# MCU.net
KiCad netlist of a schematic drawn in Altium Designer
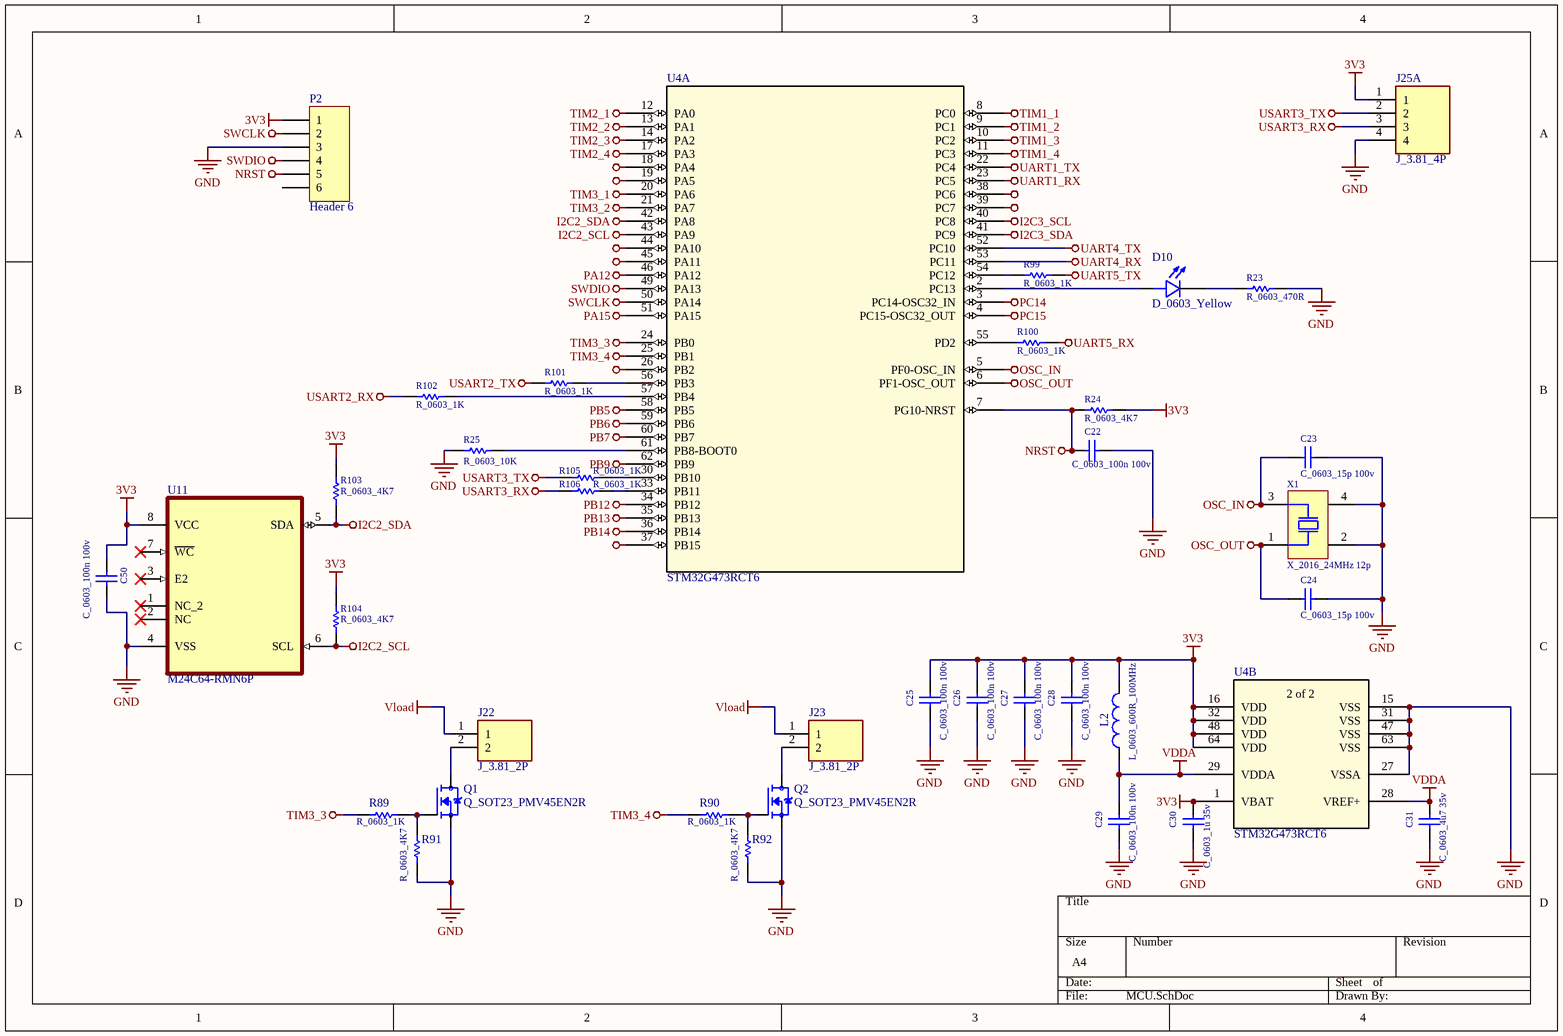
[diagram p0: MCU.SchDoc]

(export (version "E")
  (design (tool "Eeschema 10.0.6"))
  (components
    (comp (ref "C22")
      (value "C_0603_100n 100v")
      (footprint "CAP 0603")
      (description "Capacitor")
      (fields (field (name "PUBLISHER") "Altium Limited"))
      (libsource (lib "HUE") (part "Cap"))
    )
    (comp (ref "C23")
      (value "C_0603_15p 100v")
      (footprint "CAP 0603")
      (description "Capacitor")
      (fields (field (name "PUBLISHER") "Altium Limited"))
      (libsource (lib "HUE") (part "Cap"))
    )
    (comp (ref "C24")
      (value "C_0603_15p 100v")
      (footprint "CAP 0603")
      (description "Capacitor")
      (fields (field (name "PUBLISHER") "Altium Limited"))
      (libsource (lib "HUE") (part "Cap"))
    )
    (comp (ref "C25")
      (value "C_0603_100n 100v")
      (footprint "CAP 0603")
      (description "Capacitor")
      (fields (field (name "PUBLISHER") "Altium Limited"))
      (libsource (lib "HUE") (part "Cap"))
    )
    (comp (ref "C26")
      (value "C_0603_100n 100v")
      (footprint "CAP 0603")
      (description "Capacitor")
      (fields (field (name "PUBLISHER") "Altium Limited"))
      (libsource (lib "HUE") (part "Cap"))
    )
    (comp (ref "C27")
      (value "C_0603_100n 100v")
      (footprint "CAP 0603")
      (description "Capacitor")
      (fields (field (name "PUBLISHER") "Altium Limited"))
      (libsource (lib "HUE") (part "Cap"))
    )
    (comp (ref "C28")
      (value "C_0603_100n 100v")
      (footprint "CAP 0603")
      (description "Capacitor")
      (fields (field (name "PUBLISHER") "Altium Limited"))
      (libsource (lib "HUE") (part "Cap"))
    )
    (comp (ref "C29")
      (value "C_0603_100n 100v")
      (footprint "CAP 0603")
      (description "Capacitor")
      (fields (field (name "PUBLISHER") "Altium Limited"))
      (libsource (lib "HUE") (part "Cap"))
    )
    (comp (ref "C30")
      (value "C_0603_1u 35v")
      (footprint "CAP 0603")
      (description "Capacitor")
      (fields (field (name "PUBLISHER") "Altium Limited"))
      (libsource (lib "HUE") (part "Cap"))
    )
    (comp (ref "C31")
      (value "C_0603_4u7 35v")
      (footprint "CAP 0603")
      (description "Capacitor")
      (fields (field (name "PUBLISHER") "Altium Limited"))
      (libsource (lib "HUE") (part "Cap"))
    )
    (comp (ref "C50")
      (value "C_0603_100n 100v")
      (footprint "CAP 0603")
      (description "Capacitor")
      (fields (field (name "PUBLISHER") "Altium Limited"))
      (libsource (lib "HUE") (part "Cap"))
    )
    (comp (ref "D10")
      (value "D_0603_Yellow")
      (footprint "Led 0603")
      (description "Led")
      (fields (field (name "MP") "SML-D12FWT86") (field (name "MF") "Rohm"))
      (libsource (lib "HUE") (part "Led"))
    )
    (comp (ref "J22")
      (value "J_3.81_2P")
      (footprint "2 Pin PCB TB 3.81")
      (fields (field (name "MF") "CUI Devices") (field (name "MP") "TBP02R1-381-02BE"))
      (libsource (lib "HUE") (part "2 Pin PCB Terminal Block"))
    )
    (comp (ref "J23")
      (value "J_3.81_2P")
      (footprint "2 Pin PCB TB 3.81")
      (fields (field (name "MF") "CUI Devices") (field (name "MP") "TBP02R1-381-02BE"))
      (libsource (lib "HUE") (part "2 Pin PCB Terminal Block"))
    )
    (comp (ref "J25")
      (value "J_3.81_4P")
      (footprint "4 Pin PCB TB 3.81")
      (fields (field (name "MP") "TBP02R1-381-04BE"))
      (libsource (lib "HUE") (part "4 Pin PCB Terminal Block"))
    )
    (comp (ref "L2")
      (value "L_0603_600R_100MHz")
      (footprint "Inductor 0603")
      (description "Inductor")
      (fields (field (name "PUBLISHER") "Altium Limited"))
      (libsource (lib "HUE") (part "Inductor"))
    )
    (comp (ref "P2")
      (value "Header 6")
      (footprint "HDR1X6")
      (description "Header, 6-Pin")
      (fields (field (name "PUBLISHER") "Altium Limited"))
      (libsource (lib "Miscellaneous Connectors") (part "Header 6"))
    )
    (comp (ref "Q1")
      (value "Q_SOT23_PMV45EN2R")
      (footprint "SOT23")
      (fields (field (name "MP") "IRLR2705PBF") (field (name "MF") "Infineon Technologies"))
      (libsource (lib "HUE") (part "N Channel Mosfet"))
    )
    (comp (ref "Q2")
      (value "Q_SOT23_PMV45EN2R")
      (footprint "SOT23")
      (fields (field (name "MP") "IRLR2705PBF") (field (name "MF") "Infineon Technologies"))
      (libsource (lib "HUE") (part "N Channel Mosfet"))
    )
    (comp (ref "R23")
      (value "R_0603_470R")
      (footprint "RES 0603")
      (description "Resistor")
      (fields (field (name "PUBLISHER") "Altium Limited"))
      (libsource (lib "HUE") (part "Res"))
    )
    (comp (ref "R24")
      (value "R_0603_4K7")
      (footprint "RES 0603")
      (description "Resistor")
      (fields (field (name "PUBLISHER") "Altium Limited"))
      (libsource (lib "HUE") (part "Res"))
    )
    (comp (ref "R25")
      (value "R_0603_10K")
      (footprint "RES 0603")
      (description "Resistor")
      (fields (field (name "PUBLISHER") "Altium Limited"))
      (libsource (lib "HUE") (part "Res"))
    )
    (comp (ref "R89")
      (value "R_0603_1K")
      (footprint "RES 0603")
      (description "Resistor")
      (fields (field (name "PUBLISHER") "Altium Limited"))
      (libsource (lib "HUE") (part "Res"))
    )
    (comp (ref "R90")
      (value "R_0603_1K")
      (footprint "RES 0603")
      (description "Resistor")
      (fields (field (name "PUBLISHER") "Altium Limited"))
      (libsource (lib "HUE") (part "Res"))
    )
    (comp (ref "R91")
      (value "R_0603_4K7")
      (footprint "RES 0603")
      (description "Resistor")
      (fields (field (name "PUBLISHER") "Altium Limited"))
      (libsource (lib "HUE") (part "Res"))
    )
    (comp (ref "R92")
      (value "R_0603_4K7")
      (footprint "RES 0603")
      (description "Resistor")
      (fields (field (name "PUBLISHER") "Altium Limited"))
      (libsource (lib "HUE") (part "Res"))
    )
    (comp (ref "R99")
      (value "R_0603_1K")
      (footprint "RES 0603")
      (description "Resistor")
      (fields (field (name "PUBLISHER") "Altium Limited"))
      (libsource (lib "HUE") (part "Res"))
    )
    (comp (ref "R100")
      (value "R_0603_1K")
      (footprint "RES 0603")
      (description "Resistor")
      (fields (field (name "PUBLISHER") "Altium Limited"))
      (libsource (lib "HUE") (part "Res"))
    )
    (comp (ref "R101")
      (value "R_0603_1K")
      (footprint "RES 0603")
      (description "Resistor")
      (fields (field (name "PUBLISHER") "Altium Limited"))
      (libsource (lib "HUE") (part "Res"))
    )
    (comp (ref "R102")
      (value "R_0603_1K")
      (footprint "RES 0603")
      (description "Resistor")
      (fields (field (name "PUBLISHER") "Altium Limited"))
      (libsource (lib "HUE") (part "Res"))
    )
    (comp (ref "R103")
      (value "R_0603_4K7")
      (footprint "RES 0603")
      (description "Resistor")
      (fields (field (name "PUBLISHER") "Altium Limited"))
      (libsource (lib "HUE") (part "Res"))
    )
    (comp (ref "R104")
      (value "R_0603_4K7")
      (footprint "RES 0603")
      (description "Resistor")
      (fields (field (name "PUBLISHER") "Altium Limited"))
      (libsource (lib "HUE") (part "Res"))
    )
    (comp (ref "R105")
      (value "R_0603_1K")
      (footprint "RES 0603")
      (description "Resistor")
      (fields (field (name "PUBLISHER") "Altium Limited"))
      (libsource (lib "HUE") (part "Res"))
    )
    (comp (ref "R106")
      (value "R_0603_1K")
      (footprint "RES 0603")
      (description "Resistor")
      (fields (field (name "PUBLISHER") "Altium Limited"))
      (libsource (lib "HUE") (part "Res"))
    )
    (comp (ref "U4")
      (value "STM32G473RCT6")
      (footprint "LQFP64")
      (description "No Description Available")
      (libsource (lib "HUE") (part "STM32G473RCT6"))
    )
    (comp (ref "U11")
      (value "M24C64-RMN6P")
      (footprint "SOIC8 - NO-EXP")
      (description "EEPROM")
      (libsource (lib "HUE") (part "M24C64-RMN6P"))
    )
    (comp (ref "X1")
      (value "X_2016_24MHz 12p")
      (footprint "Crystal 2016")
      (description "Crystal 4 Pin")
      (libsource (lib "HUE") (part "Crystal 4 Pin"))
    )
  )
  (nets
    (net (code "1") (name "3V3") (class "Default")
      (node (ref "C25") (pin "2") (pinfunction "2_2") (pintype "passive"))
      (node (ref "C26") (pin "2") (pinfunction "2_2") (pintype "passive"))
      (node (ref "C27") (pin "2") (pinfunction "2_2") (pintype "passive"))
      (node (ref "C28") (pin "2") (pinfunction "2_2") (pintype "passive"))
      (node (ref "C30") (pin "1") (pinfunction "1_1") (pintype "passive"))
      (node (ref "C50") (pin "1") (pinfunction "1_1") (pintype "passive"))
      (node (ref "J25") (pin "1") (pinfunction "1_1") (pintype "passive"))
      (node (ref "L2") (pin "2") (pinfunction "2_2") (pintype "passive"))
      (node (ref "P2") (pin "1") (pinfunction "1_1") (pintype "passive"))
      (node (ref "R103") (pin "2") (pinfunction "2_2") (pintype "passive"))
      (node (ref "R104") (pin "2") (pinfunction "2_2") (pintype "passive"))
      (node (ref "R24") (pin "1") (pinfunction "1_1") (pintype "passive"))
      (node (ref "U11") (pin "8") (pinfunction "VCC_8") (pintype "power_in"))
      (node (ref "U4") (pin "1") (pinfunction "VBAT_1") (pintype "power_in"))
      (node (ref "U4") (pin "16") (pinfunction "VDD_16") (pintype "power_in"))
      (node (ref "U4") (pin "32") (pinfunction "VDD_32") (pintype "power_in"))
      (node (ref "U4") (pin "48") (pinfunction "VDD_48") (pintype "power_in"))
      (node (ref "U4") (pin "64") (pinfunction "VDD_64") (pintype "power_in"))
    )
    (net (code "2") (name "<NO NET>") (class "Default")
      (node (ref "U4") (pin "18") (pinfunction "PA4_18") (pintype "bidirectional"))
      (node (ref "U4") (pin "19") (pinfunction "PA5_19") (pintype "bidirectional"))
      (node (ref "U4") (pin "26") (pinfunction "PB2_26") (pintype "bidirectional"))
      (node (ref "U4") (pin "37") (pinfunction "PB15_37") (pintype "bidirectional"))
      (node (ref "U4") (pin "38") (pinfunction "PC6_38") (pintype "bidirectional"))
      (node (ref "U4") (pin "39") (pinfunction "PC7_39") (pintype "bidirectional"))
      (node (ref "U4") (pin "44") (pinfunction "PA10_44") (pintype "bidirectional"))
      (node (ref "U4") (pin "45") (pinfunction "PA11_45") (pintype "bidirectional"))
    )
    (net (code "3") (name "GND") (class "Default")
      (node (ref "C22") (pin "1") (pinfunction "1_1") (pintype "passive"))
      (node (ref "C23") (pin "1") (pinfunction "1_1") (pintype "passive"))
      (node (ref "C24") (pin "1") (pinfunction "1_1") (pintype "passive"))
      (node (ref "C25") (pin "1") (pinfunction "1_1") (pintype "passive"))
      (node (ref "C26") (pin "1") (pinfunction "1_1") (pintype "passive"))
      (node (ref "C27") (pin "1") (pinfunction "1_1") (pintype "passive"))
      (node (ref "C28") (pin "1") (pinfunction "1_1") (pintype "passive"))
      (node (ref "C29") (pin "2") (pinfunction "2_2") (pintype "passive"))
      (node (ref "C30") (pin "2") (pinfunction "2_2") (pintype "passive"))
      (node (ref "C31") (pin "2") (pinfunction "2_2") (pintype "passive"))
      (node (ref "C50") (pin "2") (pinfunction "2_2") (pintype "passive"))
      (node (ref "J25") (pin "4") (pinfunction "4_4") (pintype "passive"))
      (node (ref "P2") (pin "3") (pinfunction "3_3") (pintype "passive"))
      (node (ref "Q1") (pin "2") (pinfunction "S_2") (pintype "passive"))
      (node (ref "Q2") (pin "2") (pinfunction "S_2") (pintype "passive"))
      (node (ref "R23") (pin "1") (pinfunction "1_1") (pintype "passive"))
      (node (ref "R25") (pin "1") (pinfunction "1_1") (pintype "passive"))
      (node (ref "R91") (pin "1") (pinfunction "1_1") (pintype "passive"))
      (node (ref "R92") (pin "1") (pinfunction "1_1") (pintype "passive"))
      (node (ref "U11") (pin "4") (pinfunction "VSS_4") (pintype "passive"))
      (node (ref "U4") (pin "15") (pinfunction "VSS_15") (pintype "power_in"))
      (node (ref "U4") (pin "27") (pinfunction "VSSA_27") (pintype "power_in"))
      (node (ref "U4") (pin "31") (pinfunction "VSS_31") (pintype "power_in"))
      (node (ref "U4") (pin "47") (pinfunction "VSS_47") (pintype "power_in"))
      (node (ref "U4") (pin "63") (pinfunction "VSS_63") (pintype "power_in"))
      (node (ref "X1") (pin "2") (pinfunction "NC_2") (pintype "passive"))
      (node (ref "X1") (pin "4") (pinfunction "NC_4") (pintype "passive"))
    )
    (net (code "4") (name "I2C2_SCL") (class "Default")
      (node (ref "R104") (pin "1") (pinfunction "1_1") (pintype "passive"))
      (node (ref "U11") (pin "6") (pinfunction "SCL_6") (pintype "input"))
      (node (ref "U4") (pin "43") (pinfunction "PA9_43") (pintype "bidirectional"))
    )
    (net (code "5") (name "I2C2_SDA") (class "Default")
      (node (ref "R103") (pin "1") (pinfunction "1_1") (pintype "passive"))
      (node (ref "U11") (pin "5") (pinfunction "SDA_5") (pintype "bidirectional"))
      (node (ref "U4") (pin "42") (pinfunction "PA8_42") (pintype "bidirectional"))
    )
    (net (code "6") (name "I2C3_SCL") (class "Default")
      (node (ref "U4") (pin "40") (pinfunction "PC8_40") (pintype "bidirectional"))
    )
    (net (code "7") (name "I2C3_SDA") (class "Default")
      (node (ref "U4") (pin "41") (pinfunction "PC9_41") (pintype "bidirectional"))
    )
    (net (code "8") (name "NRST") (class "Default")
      (node (ref "C22") (pin "2") (pinfunction "2_2") (pintype "passive"))
      (node (ref "P2") (pin "5") (pinfunction "5_5") (pintype "passive"))
      (node (ref "R24") (pin "2") (pinfunction "2_2") (pintype "passive"))
      (node (ref "U4") (pin "7") (pinfunction "PG10-NRST_7") (pintype "bidirectional"))
    )
    (net (code "9") (name "Net-(D10-A)") (class "Default")
      (node (ref "D10") (pin "1") (pinfunction "A_1") (pintype "passive"))
      (node (ref "U4") (pin "2") (pinfunction "PC13_2") (pintype "bidirectional"))
    )
    (net (code "10") (name "Net-(D10-C)") (class "Default")
      (node (ref "D10") (pin "2") (pinfunction "C_2") (pintype "passive"))
      (node (ref "R23") (pin "2") (pinfunction "2_2") (pintype "passive"))
    )
    (net (code "11") (name "Net-(Q1-D)") (class "Default")
      (node (ref "J22") (pin "2") (pinfunction "2_2") (pintype "passive"))
      (node (ref "Q1") (pin "3") (pinfunction "D_3") (pintype "passive"))
    )
    (net (code "12") (name "Net-(Q1-G)") (class "Default")
      (node (ref "Q1") (pin "1") (pinfunction "G_1") (pintype "passive"))
      (node (ref "R89") (pin "1") (pinfunction "1_1") (pintype "passive"))
      (node (ref "R91") (pin "2") (pinfunction "2_2") (pintype "passive"))
    )
    (net (code "13") (name "Net-(Q2-D)") (class "Default")
      (node (ref "J23") (pin "2") (pinfunction "2_2") (pintype "passive"))
      (node (ref "Q2") (pin "3") (pinfunction "D_3") (pintype "passive"))
    )
    (net (code "14") (name "Net-(Q2-G)") (class "Default")
      (node (ref "Q2") (pin "1") (pinfunction "G_1") (pintype "passive"))
      (node (ref "R90") (pin "1") (pinfunction "1_1") (pintype "passive"))
      (node (ref "R92") (pin "2") (pinfunction "2_2") (pintype "passive"))
    )
    (net (code "15") (name "Net-(U4A-PB3)") (class "Default")
      (node (ref "R101") (pin "1") (pinfunction "1_1") (pintype "passive"))
      (node (ref "U4") (pin "56") (pinfunction "PB3_56") (pintype "bidirectional"))
    )
    (net (code "16") (name "Net-(U4A-PB4)") (class "Default")
      (node (ref "R102") (pin "1") (pinfunction "1_1") (pintype "passive"))
      (node (ref "U4") (pin "57") (pinfunction "PB4_57") (pintype "bidirectional"))
    )
    (net (code "17") (name "Net-(U4A-PB8-BOOT0)") (class "Default")
      (node (ref "R25") (pin "2") (pinfunction "2_2") (pintype "passive"))
      (node (ref "U4") (pin "61") (pinfunction "PB8-BOOT0_61") (pintype "bidirectional"))
    )
    (net (code "18") (name "Net-(U4A-PB10)") (class "Default")
      (node (ref "R105") (pin "2") (pinfunction "2_2") (pintype "passive"))
      (node (ref "U4") (pin "30") (pinfunction "PB10_30") (pintype "bidirectional"))
    )
    (net (code "19") (name "Net-(U4A-PB11)") (class "Default")
      (node (ref "R106") (pin "2") (pinfunction "2_2") (pintype "passive"))
      (node (ref "U4") (pin "33") (pinfunction "PB11_33") (pintype "bidirectional"))
    )
    (net (code "20") (name "Net-(U4A-PC12)") (class "Default")
      (node (ref "R99") (pin "2") (pinfunction "2_2") (pintype "passive"))
      (node (ref "U4") (pin "54") (pinfunction "PC12_54") (pintype "bidirectional"))
    )
    (net (code "21") (name "Net-(U4A-PD2)") (class "Default")
      (node (ref "R100") (pin "2") (pinfunction "2_2") (pintype "passive"))
      (node (ref "U4") (pin "55") (pinfunction "PD2_55") (pintype "bidirectional"))
    )
    (net (code "22") (name "OSC_IN") (class "Default")
      (node (ref "C23") (pin "2") (pinfunction "2_2") (pintype "passive"))
      (node (ref "U4") (pin "5") (pinfunction "PF0-OSC_IN_5") (pintype "bidirectional"))
      (node (ref "X1") (pin "3") (pinfunction "OSC2_3") (pintype "passive"))
    )
    (net (code "23") (name "OSC_OUT") (class "Default")
      (node (ref "C24") (pin "2") (pinfunction "2_2") (pintype "passive"))
      (node (ref "U4") (pin "6") (pinfunction "PF1-OSC_OUT_6") (pintype "bidirectional"))
      (node (ref "X1") (pin "1") (pinfunction "OSC1_1") (pintype "passive"))
    )
    (net (code "24") (name "PA12") (class "Default")
      (node (ref "U4") (pin "46") (pinfunction "PA12_46") (pintype "bidirectional"))
    )
    (net (code "25") (name "PA15") (class "Default")
      (node (ref "U4") (pin "51") (pinfunction "PA15_51") (pintype "bidirectional"))
    )
    (net (code "26") (name "PB5") (class "Default")
      (node (ref "U4") (pin "58") (pinfunction "PB5_58") (pintype "bidirectional"))
    )
    (net (code "27") (name "PB6") (class "Default")
      (node (ref "U4") (pin "59") (pinfunction "PB6_59") (pintype "bidirectional"))
    )
    (net (code "28") (name "PB7") (class "Default")
      (node (ref "U4") (pin "60") (pinfunction "PB7_60") (pintype "bidirectional"))
    )
    (net (code "29") (name "PB9") (class "Default")
      (node (ref "U4") (pin "62") (pinfunction "PB9_62") (pintype "bidirectional"))
    )
    (net (code "30") (name "PB12") (class "Default")
      (node (ref "U4") (pin "34") (pinfunction "PB12_34") (pintype "bidirectional"))
    )
    (net (code "31") (name "PB13") (class "Default")
      (node (ref "U4") (pin "35") (pinfunction "PB13_35") (pintype "bidirectional"))
    )
    (net (code "32") (name "PB14") (class "Default")
      (node (ref "U4") (pin "36") (pinfunction "PB14_36") (pintype "bidirectional"))
    )
    (net (code "33") (name "PC14") (class "Default")
      (node (ref "U4") (pin "3") (pinfunction "PC14-OSC32_IN_3") (pintype "bidirectional"))
    )
    (net (code "34") (name "PC15") (class "Default")
      (node (ref "U4") (pin "4") (pinfunction "PC15-OSC32_OUT_4") (pintype "bidirectional"))
    )
    (net (code "35") (name "SWCLK") (class "Default")
      (node (ref "P2") (pin "2") (pinfunction "2_2") (pintype "passive"))
      (node (ref "U4") (pin "50") (pinfunction "PA14_50") (pintype "bidirectional"))
    )
    (net (code "36") (name "SWDIO") (class "Default")
      (node (ref "P2") (pin "4") (pinfunction "4_4") (pintype "passive"))
      (node (ref "U4") (pin "49") (pinfunction "PA13_49") (pintype "bidirectional"))
    )
    (net (code "37") (name "TIM1_1") (class "Default")
      (node (ref "U4") (pin "8") (pinfunction "PC0_8") (pintype "bidirectional"))
    )
    (net (code "38") (name "TIM1_2") (class "Default")
      (node (ref "U4") (pin "9") (pinfunction "PC1_9") (pintype "bidirectional"))
    )
    (net (code "39") (name "TIM1_3") (class "Default")
      (node (ref "U4") (pin "10") (pinfunction "PC2_10") (pintype "bidirectional"))
    )
    (net (code "40") (name "TIM1_4") (class "Default")
      (node (ref "U4") (pin "11") (pinfunction "PC3_11") (pintype "bidirectional"))
    )
    (net (code "41") (name "TIM2_1") (class "Default")
      (node (ref "U4") (pin "12") (pinfunction "PA0_12") (pintype "bidirectional"))
    )
    (net (code "42") (name "TIM2_2") (class "Default")
      (node (ref "U4") (pin "13") (pinfunction "PA1_13") (pintype "bidirectional"))
    )
    (net (code "43") (name "TIM2_3") (class "Default")
      (node (ref "U4") (pin "14") (pinfunction "PA2_14") (pintype "bidirectional"))
    )
    (net (code "44") (name "TIM2_4") (class "Default")
      (node (ref "U4") (pin "17") (pinfunction "PA3_17") (pintype "bidirectional"))
    )
    (net (code "45") (name "TIM3_1") (class "Default")
      (node (ref "U4") (pin "20") (pinfunction "PA6_20") (pintype "bidirectional"))
    )
    (net (code "46") (name "TIM3_2") (class "Default")
      (node (ref "U4") (pin "21") (pinfunction "PA7_21") (pintype "bidirectional"))
    )
    (net (code "47") (name "TIM3_3") (class "Default")
      (node (ref "R89") (pin "2") (pinfunction "2_2") (pintype "passive"))
      (node (ref "U4") (pin "24") (pinfunction "PB0_24") (pintype "bidirectional"))
    )
    (net (code "48") (name "TIM3_4") (class "Default")
      (node (ref "R90") (pin "2") (pinfunction "2_2") (pintype "passive"))
      (node (ref "U4") (pin "25") (pinfunction "PB1_25") (pintype "bidirectional"))
    )
    (net (code "49") (name "UART1_RX") (class "Default")
      (node (ref "U4") (pin "23") (pinfunction "PC5_23") (pintype "bidirectional"))
    )
    (net (code "50") (name "UART1_TX") (class "Default")
      (node (ref "U4") (pin "22") (pinfunction "PC4_22") (pintype "bidirectional"))
    )
    (net (code "51") (name "UART4_RX") (class "Default")
      (node (ref "U4") (pin "53") (pinfunction "PC11_53") (pintype "bidirectional"))
    )
    (net (code "52") (name "UART4_TX") (class "Default")
      (node (ref "U4") (pin "52") (pinfunction "PC10_52") (pintype "bidirectional"))
    )
    (net (code "53") (name "UART5_RX") (class "Default")
      (node (ref "R100") (pin "1") (pinfunction "1_1") (pintype "passive"))
    )
    (net (code "54") (name "UART5_TX") (class "Default")
      (node (ref "R99") (pin "1") (pinfunction "1_1") (pintype "passive"))
    )
    (net (code "55") (name "USART2_RX") (class "Default")
      (node (ref "R102") (pin "2") (pinfunction "2_2") (pintype "passive"))
    )
    (net (code "56") (name "USART2_TX") (class "Default")
      (node (ref "R101") (pin "2") (pinfunction "2_2") (pintype "passive"))
    )
    (net (code "57") (name "USART3_RX") (class "Default")
      (node (ref "J25") (pin "3") (pinfunction "3_3") (pintype "passive"))
      (node (ref "R106") (pin "1") (pinfunction "1_1") (pintype "passive"))
    )
    (net (code "58") (name "USART3_TX") (class "Default")
      (node (ref "J25") (pin "2") (pinfunction "2_2") (pintype "passive"))
      (node (ref "R105") (pin "1") (pinfunction "1_1") (pintype "passive"))
    )
    (net (code "59") (name "VDDA") (class "Default")
      (node (ref "C29") (pin "1") (pinfunction "1_1") (pintype "passive"))
      (node (ref "C31") (pin "1") (pinfunction "1_1") (pintype "passive"))
      (node (ref "L2") (pin "1") (pinfunction "1_1") (pintype "passive"))
      (node (ref "U4") (pin "28") (pinfunction "VREF+_28") (pintype "power_in"))
      (node (ref "U4") (pin "29") (pinfunction "VDDA_29") (pintype "power_in"))
    )
    (net (code "60") (name "Vload") (class "Default")
      (node (ref "J22") (pin "1") (pinfunction "1_1") (pintype "passive"))
      (node (ref "J23") (pin "1") (pinfunction "1_1") (pintype "passive"))
    )
    (net (code "61") (name "unconnected-(P2-Pad6)") (class "Default")
      (node (ref "P2") (pin "6") (pinfunction "6_6") (pintype "passive"))
    )
    (net (code "62") (name "unconnected-(U11-E2-Pad3)") (class "Default")
      (node (ref "U11") (pin "3") (pinfunction "E2_3") (pintype "input+no_connect"))
    )
    (net (code "63") (name "unconnected-(U11-NC-Pad2)") (class "Default")
      (node (ref "U11") (pin "2") (pinfunction "NC_2") (pintype "passive+no_connect"))
    )
    (net (code "64") (name "unconnected-(U11-NC_2-Pad1)") (class "Default")
      (node (ref "U11") (pin "1") (pinfunction "NC_2_1") (pintype "passive+no_connect"))
    )
    (net (code "65") (name "unconnected-(U11-~{WC}-Pad7)") (class "Default")
      (node (ref "U11") (pin "7") (pinfunction "~{WC}_7") (pintype "input+no_connect"))
    )
  )
)
